# Phantom_Controller.net
KiCad netlist of a schematic drawn in EasyEDA
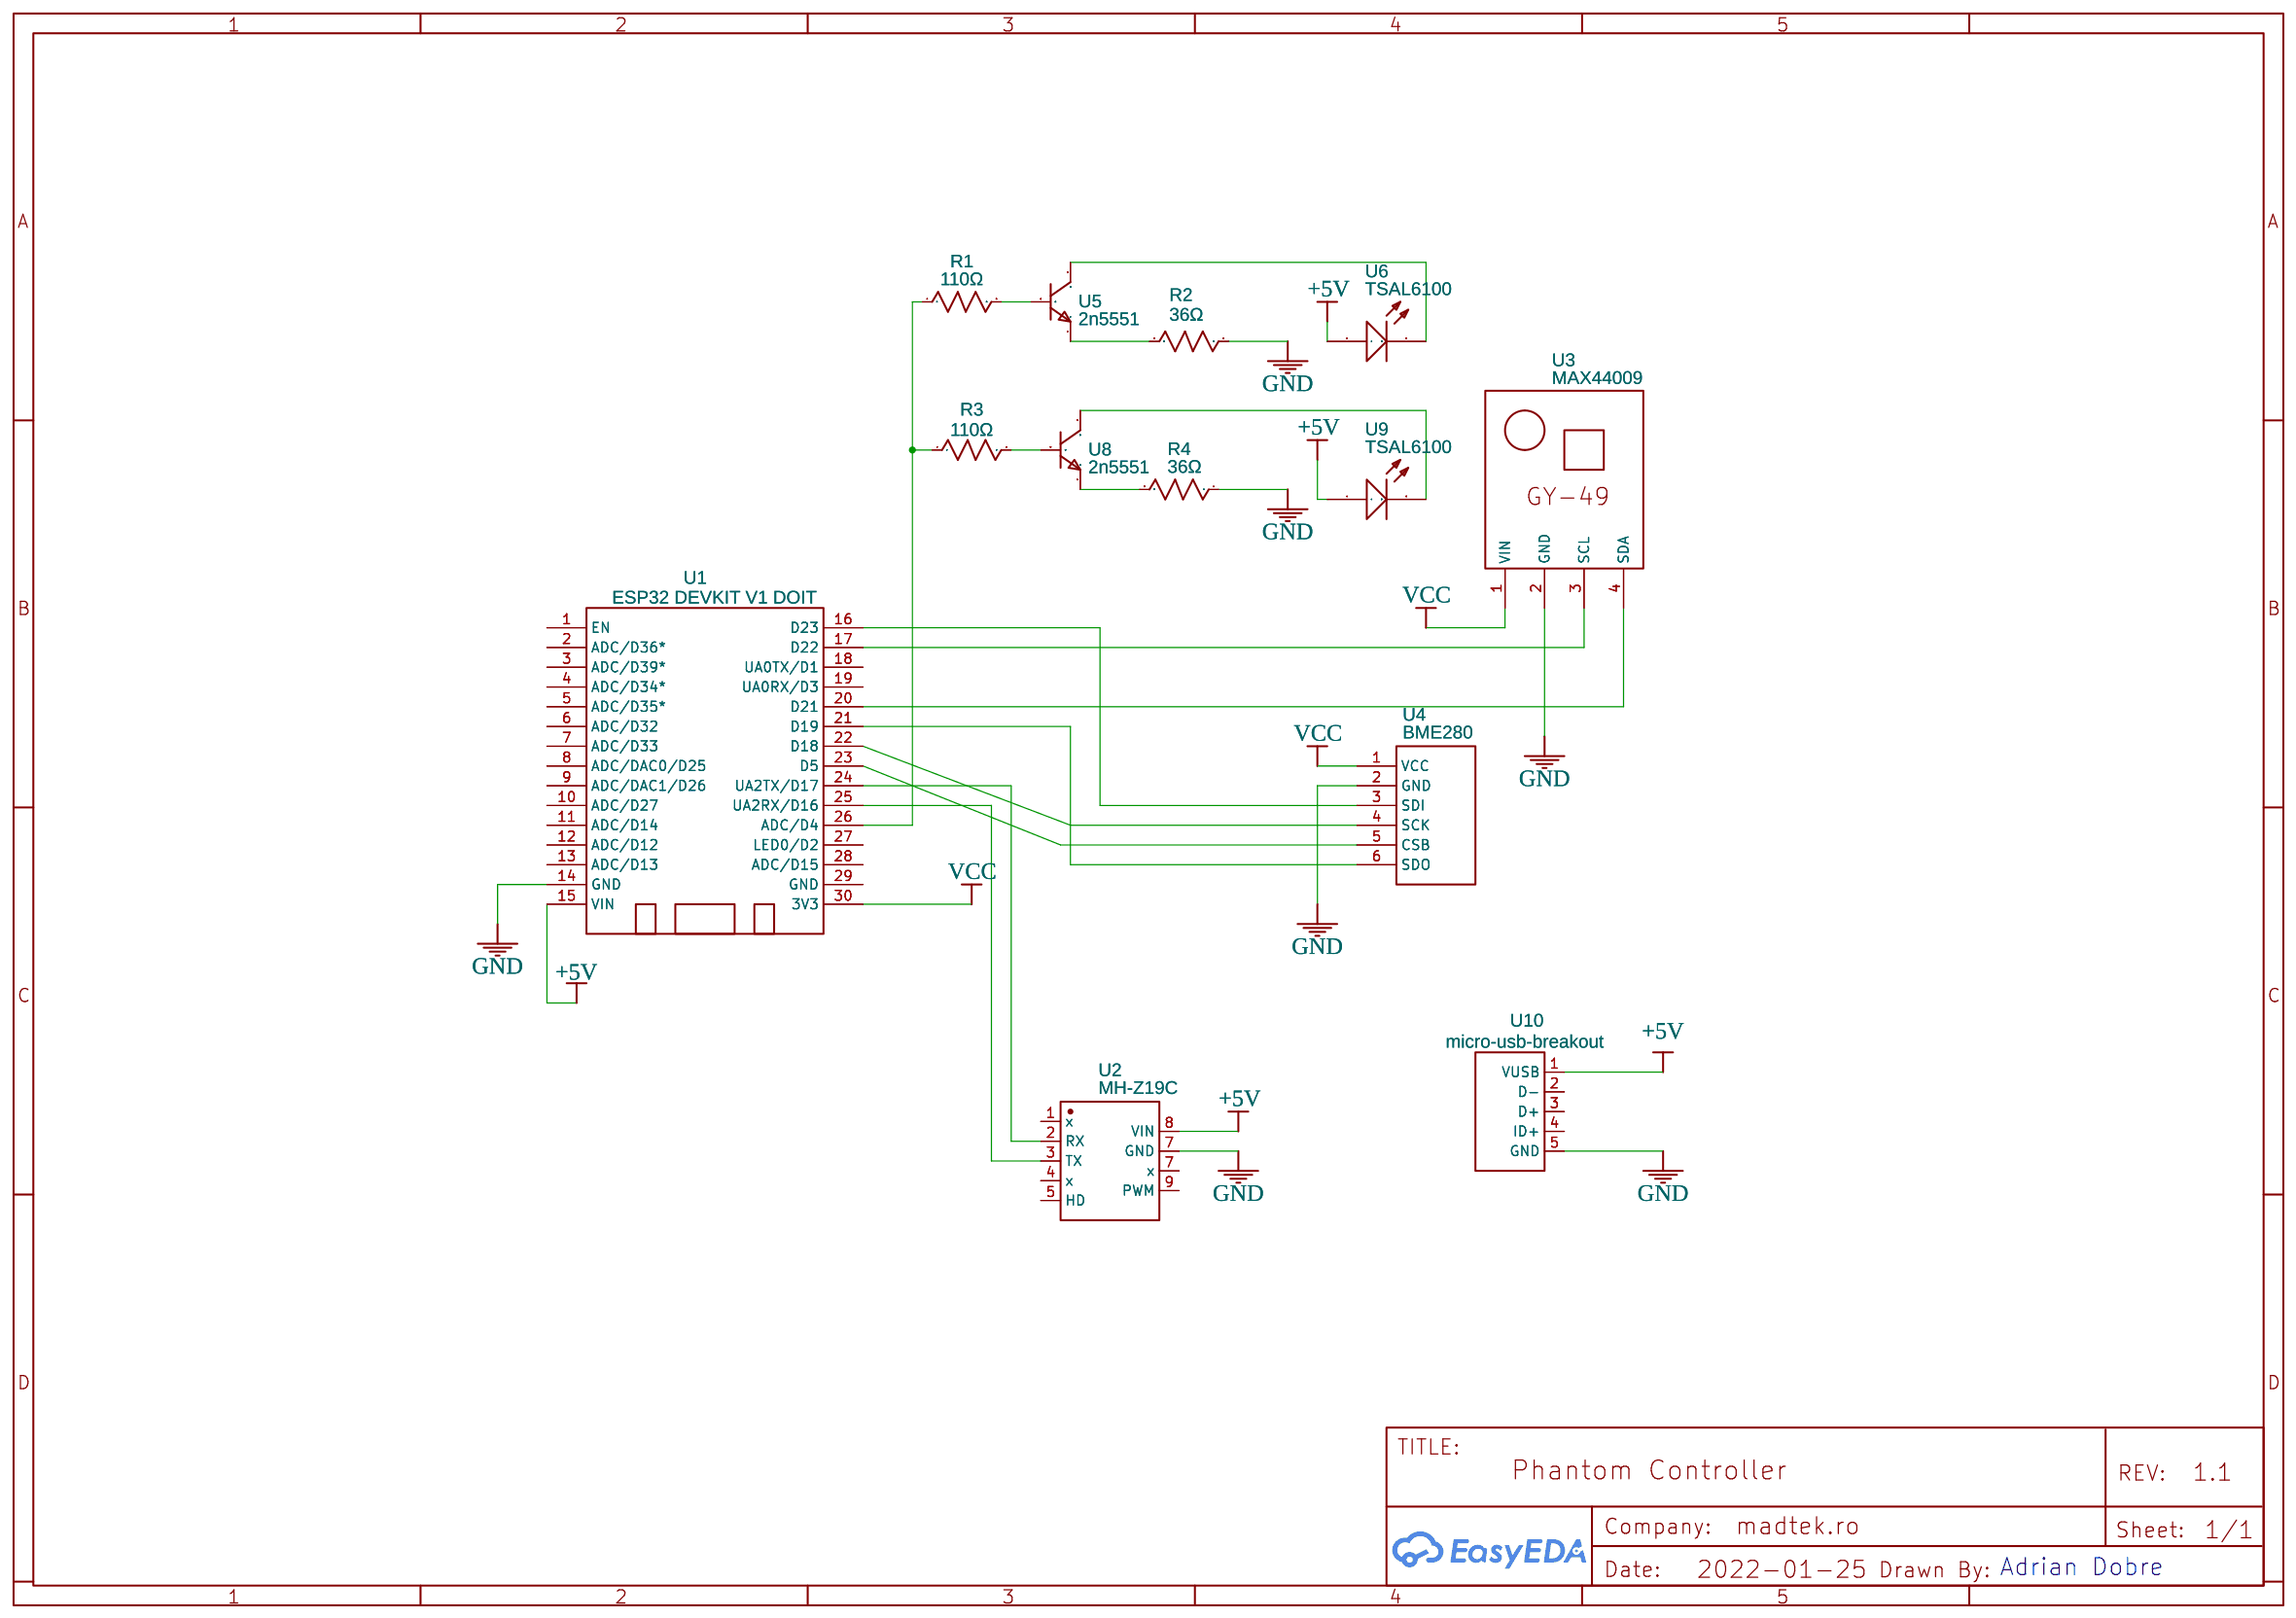
[diagram p0: schematic sheet]

(export (version "E")
  (design (tool "Eeschema 10.0.6"))
  (components
    (comp (ref "R1") (value "110Ω") (libsource (lib "") (part "Res_1")))
    (comp (ref "R2") (value "36Ω") (libsource (lib "") (part "Res")))
    (comp (ref "R3") (value "110Ω") (libsource (lib "") (part "Res_1")))
    (comp (ref "R4") (value "36Ω") (libsource (lib "") (part "Res")))
    (comp (ref "U1") (value "ESP32 DEVKIT V1 DOIT") (libsource (lib "") (part "ESP32 DEVKIT V1 DOIT")))
    (comp (ref "U2") (value "MH-Z19C") (libsource (lib "") (part "MH-Z19C_sym")))
    (comp (ref "U3")
      (value "MAX44009")
      (fields (field (name "BOM_Manufacturer Part") "BMP 280 4-PIN"))
      (libsource (lib "") (part "BMP 280 4-PIN"))
    )
    (comp (ref "U4") (value "BME280") (libsource (lib "") (part "BME280")))
    (comp (ref "U5") (value "2n5551") (libsource (lib "") (part "2n5551")))
    (comp (ref "U6")
      (value "TSAL6100")
      (fields (field (name "BOM_Supplier Part") "C111836"))
      (libsource (lib "") (part "TSAL6100"))
    )
    (comp (ref "U8") (value "2n5551") (libsource (lib "") (part "2n5551")))
    (comp (ref "U9")
      (value "TSAL6100")
      (fields (field (name "BOM_Supplier Part") "C111836"))
      (libsource (lib "") (part "TSAL6100"))
    )
    (comp (ref "U10") (value "micro-usb-breakout") (libsource (lib "") (part "micro-usb-breakout")))
  )
  (nets
    (net (code "1") (name "+5V") (class "Default")
      (node (ref "U1") (pin "15") (pinfunction "VIN_15") (pintype "input"))
      (node (ref "U10") (pin "1") (pinfunction "VUSB_1") (pintype "unspecified"))
      (node (ref "U2") (pin "8") (pinfunction "VIN_8") (pintype "unspecified"))
      (node (ref "U6") (pin "1") (pinfunction "A_1") (pintype "input"))
      (node (ref "U9") (pin "1") (pinfunction "A_1") (pintype "input"))
    )
    (net (code "2") (name "GND") (class "Default")
      (node (ref "R2") (pin "1") (pinfunction "1_1") (pintype "unspecified"))
      (node (ref "R4") (pin "1") (pinfunction "1_1") (pintype "unspecified"))
      (node (ref "U1") (pin "14") (pinfunction "GND_14") (pintype "bidirectional"))
      (node (ref "U10") (pin "5") (pinfunction "GND_5") (pintype "unspecified"))
      (node (ref "U2") (pin "7") (pinfunction "GND_7") (pintype "unspecified"))
      (node (ref "U3") (pin "2") (pinfunction "GND_2") (pintype "unspecified"))
      (node (ref "U4") (pin "2") (pinfunction "GND_2") (pintype "unspecified"))
    )
    (net (code "3") (name "Net-(U1-ADC{slash}D4)") (class "Default")
      (node (ref "R1") (pin "1") (pinfunction "1_1") (pintype "unspecified"))
      (node (ref "R3") (pin "1") (pinfunction "1_1") (pintype "unspecified"))
      (node (ref "U1") (pin "26") (pinfunction "ADC/D4_26") (pintype "bidirectional"))
    )
    (net (code "4") (name "Net-(U1-D5)") (class "Default")
      (node (ref "U1") (pin "23") (pinfunction "D5_23") (pintype "bidirectional"))
      (node (ref "U4") (pin "5") (pinfunction "CSB_5") (pintype "unspecified"))
    )
    (net (code "5") (name "Net-(U1-D18)") (class "Default")
      (node (ref "U1") (pin "22") (pinfunction "D18_22") (pintype "bidirectional"))
      (node (ref "U4") (pin "4") (pinfunction "SCK_4") (pintype "unspecified"))
    )
    (net (code "6") (name "Net-(U1-D19)") (class "Default")
      (node (ref "U1") (pin "21") (pinfunction "D19_21") (pintype "bidirectional"))
      (node (ref "U4") (pin "6") (pinfunction "SDO_6") (pintype "unspecified"))
    )
    (net (code "7") (name "Net-(U1-D21)") (class "Default")
      (node (ref "U1") (pin "20") (pinfunction "D21_20") (pintype "bidirectional"))
      (node (ref "U3") (pin "4") (pinfunction "SDA_4") (pintype "unspecified"))
    )
    (net (code "8") (name "Net-(U1-D22)") (class "Default")
      (node (ref "U1") (pin "17") (pinfunction "D22_17") (pintype "bidirectional"))
      (node (ref "U3") (pin "3") (pinfunction "SCL_3") (pintype "unspecified"))
    )
    (net (code "9") (name "Net-(U1-D23)") (class "Default")
      (node (ref "U1") (pin "16") (pinfunction "D23_16") (pintype "bidirectional"))
      (node (ref "U4") (pin "3") (pinfunction "SDI_3") (pintype "unspecified"))
    )
    (net (code "10") (name "Net-(U1-UA2RX{slash}D16)") (class "Default")
      (node (ref "U1") (pin "25") (pinfunction "UA2RX/D16_25") (pintype "bidirectional"))
      (node (ref "U2") (pin "3") (pinfunction "TX_3") (pintype "unspecified"))
    )
    (net (code "11") (name "Net-(U1-UA2TX{slash}D17)") (class "Default")
      (node (ref "U1") (pin "24") (pinfunction "UA2TX/D17_24") (pintype "bidirectional"))
      (node (ref "U2") (pin "2") (pinfunction "RX_2") (pintype "unspecified"))
    )
    (net (code "12") (name "Net-(U5-B)") (class "Default")
      (node (ref "R1") (pin "2") (pinfunction "2_2") (pintype "unspecified"))
      (node (ref "U5") (pin "3") (pinfunction "B_3") (pintype "unspecified"))
    )
    (net (code "13") (name "Net-(U5-C)") (class "Default")
      (node (ref "U5") (pin "2") (pinfunction "C_2") (pintype "unspecified"))
      (node (ref "U6") (pin "2") (pinfunction "C_2") (pintype "input"))
    )
    (net (code "14") (name "Net-(U5-E)") (class "Default")
      (node (ref "R2") (pin "2") (pinfunction "2_2") (pintype "unspecified"))
      (node (ref "U5") (pin "1") (pinfunction "E_1") (pintype "unspecified"))
    )
    (net (code "15") (name "Net-(U8-B)") (class "Default")
      (node (ref "R3") (pin "2") (pinfunction "2_2") (pintype "unspecified"))
      (node (ref "U8") (pin "3") (pinfunction "B_3") (pintype "unspecified"))
    )
    (net (code "16") (name "Net-(U8-C)") (class "Default")
      (node (ref "U8") (pin "2") (pinfunction "C_2") (pintype "unspecified"))
      (node (ref "U9") (pin "2") (pinfunction "C_2") (pintype "input"))
    )
    (net (code "17") (name "Net-(U8-E)") (class "Default")
      (node (ref "R4") (pin "2") (pinfunction "2_2") (pintype "unspecified"))
      (node (ref "U8") (pin "1") (pinfunction "E_1") (pintype "unspecified"))
    )
    (net (code "18") (name "VCC") (class "Default")
      (node (ref "U1") (pin "30") (pinfunction "3V3_30") (pintype "bidirectional"))
      (node (ref "U3") (pin "1") (pinfunction "VIN_1") (pintype "unspecified"))
      (node (ref "U4") (pin "1") (pinfunction "VCC_1") (pintype "unspecified"))
    )
    (net (code "19") (name "unconnected-(U1-ADC{slash}D12-Pad12)") (class "Default")
      (node (ref "U1") (pin "12") (pinfunction "ADC/D12_12") (pintype "bidirectional"))
    )
    (net (code "20") (name "unconnected-(U1-ADC{slash}D13-Pad13)") (class "Default")
      (node (ref "U1") (pin "13") (pinfunction "ADC/D13_13") (pintype "bidirectional"))
    )
    (net (code "21") (name "unconnected-(U1-ADC{slash}D14-Pad11)") (class "Default")
      (node (ref "U1") (pin "11") (pinfunction "ADC/D14_11") (pintype "bidirectional"))
    )
    (net (code "22") (name "unconnected-(U1-ADC{slash}D15-Pad28)") (class "Default")
      (node (ref "U1") (pin "28") (pinfunction "ADC/D15_28") (pintype "bidirectional"))
    )
    (net (code "23") (name "unconnected-(U1-ADC{slash}D27-Pad10)") (class "Default")
      (node (ref "U1") (pin "10") (pinfunction "ADC/D27_10") (pintype "bidirectional"))
    )
    (net (code "24") (name "unconnected-(U1-ADC{slash}D32-Pad6)") (class "Default")
      (node (ref "U1") (pin "6") (pinfunction "ADC/D32_6") (pintype "bidirectional"))
    )
    (net (code "25") (name "unconnected-(U1-ADC{slash}D33-Pad7)") (class "Default")
      (node (ref "U1") (pin "7") (pinfunction "ADC/D33_7") (pintype "bidirectional"))
    )
    (net (code "26") (name "unconnected-(U1-ADC{slash}D34*-Pad4)") (class "Default")
      (node (ref "U1") (pin "4") (pinfunction "ADC/D34*_4") (pintype "input"))
    )
    (net (code "27") (name "unconnected-(U1-ADC{slash}D35*-Pad5)") (class "Default")
      (node (ref "U1") (pin "5") (pinfunction "ADC/D35*_5") (pintype "input"))
    )
    (net (code "28") (name "unconnected-(U1-ADC{slash}D36*-Pad2)") (class "Default")
      (node (ref "U1") (pin "2") (pinfunction "ADC/D36*_2") (pintype "input"))
    )
    (net (code "29") (name "unconnected-(U1-ADC{slash}D39*-Pad3)") (class "Default")
      (node (ref "U1") (pin "3") (pinfunction "ADC/D39*_3") (pintype "input"))
    )
    (net (code "30") (name "unconnected-(U1-ADC{slash}DAC0{slash}D25-Pad8)") (class "Default")
      (node (ref "U1") (pin "8") (pinfunction "ADC/DAC0/D25_8") (pintype "bidirectional"))
    )
    (net (code "31") (name "unconnected-(U1-ADC{slash}DAC1{slash}D26-Pad9)") (class "Default")
      (node (ref "U1") (pin "9") (pinfunction "ADC/DAC1/D26_9") (pintype "bidirectional"))
    )
    (net (code "32") (name "unconnected-(U1-EN-Pad1)") (class "Default")
      (node (ref "U1") (pin "1") (pinfunction "EN_1") (pintype "bidirectional"))
    )
    (net (code "33") (name "unconnected-(U1-GND-Pad29)") (class "Default")
      (node (ref "U1") (pin "29") (pinfunction "GND_29") (pintype "bidirectional"))
    )
    (net (code "34") (name "unconnected-(U1-LED0{slash}D2-Pad27)") (class "Default")
      (node (ref "U1") (pin "27") (pinfunction "LED0/D2_27") (pintype "bidirectional"))
    )
    (net (code "35") (name "unconnected-(U1-UA0RX{slash}D3-Pad19)") (class "Default")
      (node (ref "U1") (pin "19") (pinfunction "UA0RX/D3_19") (pintype "bidirectional"))
    )
    (net (code "36") (name "unconnected-(U1-UA0TX{slash}D1-Pad18)") (class "Default")
      (node (ref "U1") (pin "18") (pinfunction "UA0TX/D1_18") (pintype "bidirectional"))
    )
    (net (code "37") (name "unconnected-(U2-HD-Pad5)") (class "Default")
      (node (ref "U2") (pin "5") (pinfunction "HD_5") (pintype "unspecified"))
    )
    (net (code "38") (name "unconnected-(U2-PWM-Pad9)") (class "Default")
      (node (ref "U2") (pin "9") (pinfunction "PWM_9") (pintype "unspecified"))
    )
    (net (code "39") (name "unconnected-(U2-x-Pad1)") (class "Default")
      (node (ref "U2") (pin "1") (pinfunction "x_1") (pintype "unspecified"))
    )
    (net (code "40") (name "unconnected-(U2-x-Pad4)") (class "Default")
      (node (ref "U2") (pin "4") (pinfunction "x_4") (pintype "unspecified"))
    )
    (net (code "41") (name "unconnected-(U2-x-Pad7)") (class "Default")
      (node (ref "U2") (pin "7") (pinfunction "x_7") (pintype "unspecified"))
    )
    (net (code "42") (name "unconnected-(U10-D+-Pad3)") (class "Default")
      (node (ref "U10") (pin "3") (pinfunction "D+_3") (pintype "unspecified"))
    )
    (net (code "43") (name "unconnected-(U10-D--Pad2)") (class "Default")
      (node (ref "U10") (pin "2") (pinfunction "D-_2") (pintype "unspecified"))
    )
    (net (code "44") (name "unconnected-(U10-ID+-Pad4)") (class "Default")
      (node (ref "U10") (pin "4") (pinfunction "ID+_4") (pintype "unspecified"))
    )
  )
)
